# VoltageDivider.net
KiCad netlist of a schematic drawn in Altium Designer
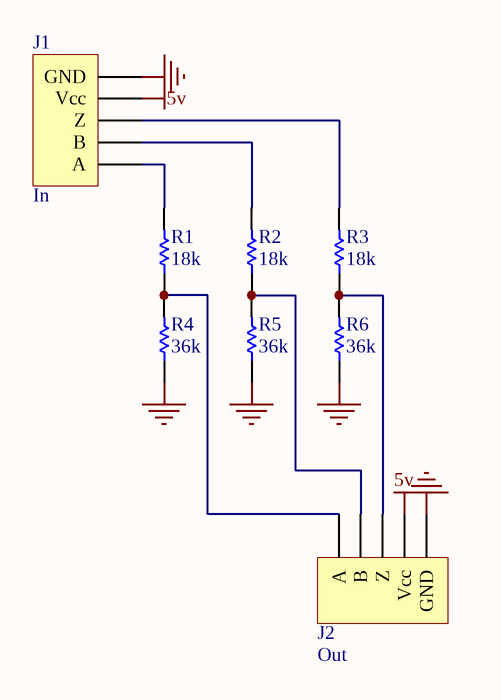
[diagram p0: VoltageDivider.SchDoc]

(export (version "E")
  (design (tool "Eeschema 10.0.6"))
  (components
    (comp (ref "J1")
      (value "In")
      (footprint "HDR1X5")
      (description "Header, 5-Pin")
      (fields (field (name "PUBLISHER") "Altium Limited"))
      (libsource (lib "Miscellaneous Connectors") (part "Header 5"))
    )
    (comp (ref "J2")
      (value "Out")
      (footprint "HDR1X5")
      (description "Header, 5-Pin")
      (fields (field (name "PUBLISHER") "Altium Limited"))
      (libsource (lib "Miscellaneous Connectors") (part "Header 5"))
    )
    (comp (ref "R1")
      (value "18k")
      (footprint "Res SMD 0805A")
      (fields (field (name "Comment") "Res1"))
      (libsource (lib "Custom") (part "Resistor"))
    )
    (comp (ref "R2")
      (value "18k")
      (footprint "Res SMD 0805A")
      (fields (field (name "Comment") "Res1"))
      (libsource (lib "Custom") (part "Resistor"))
    )
    (comp (ref "R3")
      (value "18k")
      (footprint "Res SMD 0805A")
      (fields (field (name "Comment") "Res1"))
      (libsource (lib "Custom") (part "Resistor"))
    )
    (comp (ref "R4")
      (value "36k")
      (footprint "Res SMD 0805A")
      (fields (field (name "Comment") "Res1"))
      (libsource (lib "Custom") (part "Resistor"))
    )
    (comp (ref "R5")
      (value "36k")
      (footprint "Res SMD 0805A")
      (fields (field (name "Comment") "Res1"))
      (libsource (lib "Custom") (part "Resistor"))
    )
    (comp (ref "R6")
      (value "36k")
      (footprint "Res SMD 0805A")
      (fields (field (name "Comment") "Res1"))
      (libsource (lib "Custom") (part "Resistor"))
    )
  )
  (nets
    (net (code "1") (name "5v") (class "Default")
      (node (ref "J1") (pin "4") (pinfunction "Vcc_4") (pintype "passive"))
      (node (ref "J2") (pin "4") (pinfunction "Vcc_4") (pintype "passive"))
    )
    (net (code "2") (name "GND") (class "Default")
      (node (ref "J1") (pin "5") (pinfunction "GND_5") (pintype "passive"))
      (node (ref "J2") (pin "5") (pinfunction "GND_5") (pintype "passive"))
      (node (ref "R4") (pin "1") (pinfunction "1_1") (pintype "passive"))
      (node (ref "R5") (pin "1") (pinfunction "1_1") (pintype "passive"))
      (node (ref "R6") (pin "1") (pinfunction "1_1") (pintype "passive"))
    )
    (net (code "3") (name "Net-(J1-A)") (class "Default")
      (node (ref "J1") (pin "1") (pinfunction "A_1") (pintype "passive"))
      (node (ref "R1") (pin "2") (pinfunction "2_2") (pintype "passive"))
    )
    (net (code "4") (name "Net-(J1-B)") (class "Default")
      (node (ref "J1") (pin "2") (pinfunction "B_2") (pintype "passive"))
      (node (ref "R2") (pin "2") (pinfunction "2_2") (pintype "passive"))
    )
    (net (code "5") (name "Net-(J1-Z)") (class "Default")
      (node (ref "J1") (pin "3") (pinfunction "Z_3") (pintype "passive"))
      (node (ref "R3") (pin "2") (pinfunction "2_2") (pintype "passive"))
    )
    (net (code "6") (name "Net-(J2-A)") (class "Default")
      (node (ref "J2") (pin "1") (pinfunction "A_1") (pintype "passive"))
      (node (ref "R1") (pin "1") (pinfunction "1_1") (pintype "passive"))
      (node (ref "R4") (pin "2") (pinfunction "2_2") (pintype "passive"))
    )
    (net (code "7") (name "Net-(J2-B)") (class "Default")
      (node (ref "J2") (pin "2") (pinfunction "B_2") (pintype "passive"))
      (node (ref "R2") (pin "1") (pinfunction "1_1") (pintype "passive"))
      (node (ref "R5") (pin "2") (pinfunction "2_2") (pintype "passive"))
    )
    (net (code "8") (name "Net-(J2-Z)") (class "Default")
      (node (ref "J2") (pin "3") (pinfunction "Z_3") (pintype "passive"))
      (node (ref "R3") (pin "1") (pinfunction "1_1") (pintype "passive"))
      (node (ref "R6") (pin "2") (pinfunction "2_2") (pintype "passive"))
    )
  )
)
